# MCU.net
KiCad netlist of a schematic drawn in Altium Designer
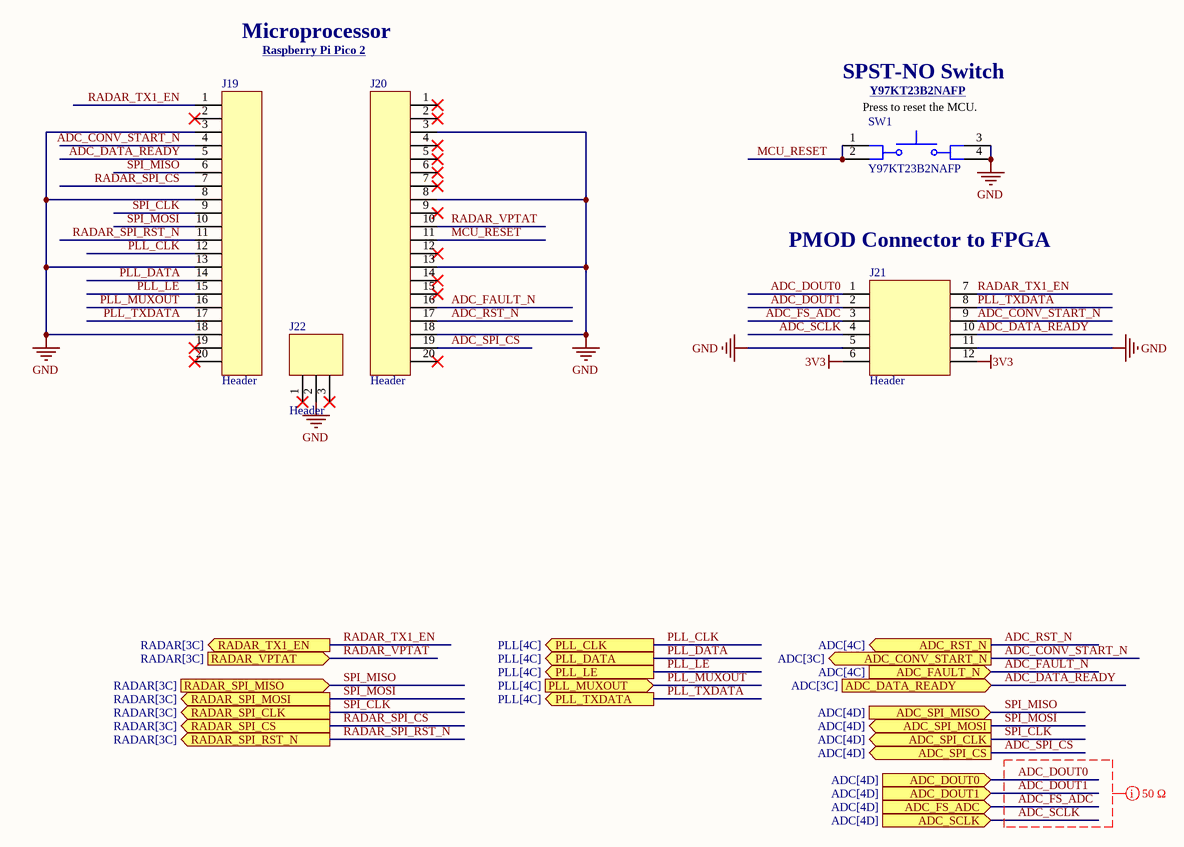
[diagram p0: MCU.SchDoc]

(export (version "E")
  (design (tool "Eeschema 10.0.6"))
  (components
    (comp (ref "J19")
      (value "Header")
      (footprint "CONN_1x20_2.54mm_PinSocket_Vertical")
      (description "WR-PHD 2.54 mm Socket Header; 20 pins")
      (fields
        (field (name "MANUFACTURER") "Wurth Elektronik")
        (field (name "MANUFACTURER PART NUMBER") "61302011821")
      )
      (libsource (lib "Titan") (part "CONN_1x20_2.54mm_PinSocket_Vertical"))
    )
    (comp (ref "J20")
      (value "Header")
      (footprint "CONN_1x20_2.54mm_PinSocket_Vertical")
      (description "WR-PHD 2.54 mm Socket Header; 20 pins")
      (fields
        (field (name "MANUFACTURER") "Wurth Elektronik")
        (field (name "MANUFACTURER PART NUMBER") "61302011821")
      )
      (libsource (lib "") (part "CONN_1x20_2.54mm_PinSocket_Vertical_1"))
    )
    (comp (ref "J21")
      (value "Header")
      (footprint "CONN_2x6_2.54mm_PinHeader_Horizontal")
      (description "Conn Unshrouded Header HDR 12 POS 2.54mm Solder RA Top Entry Thru-Hole Bag")
      (fields
        (field (name "MANUFACTURER") "Adam Tech")
        (field (name "MANUFACTURER PART NUMBER") "PH2RA-12-UA")
      )
      (libsource (lib "Titan") (part "CONN_2x6_2.54mm_PinHeader_Horizontal"))
    )
    (comp (ref "J22")
      (value "Header")
      (footprint "CONN_1x3_2.54mm_PinSocket_Vertical")
      (description "Btb Conn, Rcpt, 3Pos, 1Row, 2.54Mm Rohs Compliant: Yes ¦Wurth Elektronik 61300311821")
      (fields
        (field (name "MANUFACTURER") "Wurth Elektronik")
        (field (name "MANUFACTURER PART NUMBER") "61300311821")
      )
      (libsource (lib "Titan") (part "CONN_1x3_2.54mm_PinSocket_Vertical"))
    )
    (comp (ref "SW1")
      (value "Y97KT23B2NAFP")
      (footprint "PTS647")
      (description "Switch Tactile OFF Mom SPST Round Button Gull Wing 50mA 12VDC 100000Cycles 1.77N Surface Mount T/R")
      (fields (field (name "MANUFACTURER") "C&K"))
      (libsource (lib "Titan") (part "Y97KT23B2NAFP"))
    )
  )
  (nets
    (net (code "1") (name "/ADC_CONV_START_N") (class "Default")
      (node (ref "J19") (pin "4") (pintype "passive"))
      (node (ref "J21") (pin "9") (pintype "passive"))
    )
    (net (code "2") (name "/ADC_DATA_READY") (class "Default")
      (node (ref "J19") (pin "5") (pintype "passive"))
      (node (ref "J21") (pin "10") (pintype "passive"))
    )
    (net (code "3") (name "/ADC_DOUT0") (class "Default") (node (ref "J21") (pin "1") (pintype "passive")))
    (net (code "4") (name "/ADC_DOUT1") (class "Default") (node (ref "J21") (pin "2") (pintype "passive")))
    (net (code "5") (name "/ADC_FAULT_N") (class "Default") (node (ref "J20") (pin "16") (pintype "passive")))
    (net (code "6") (name "/ADC_FS_ADC") (class "Default") (node (ref "J21") (pin "3") (pintype "passive")))
    (net (code "7") (name "/ADC_RST_N") (class "Default") (node (ref "J20") (pin "17") (pintype "passive")))
    (net (code "8") (name "/ADC_SCLK") (class "Default") (node (ref "J21") (pin "4") (pintype "passive")))
    (net (code "9") (name "/ADC_SPI_CS") (class "Default") (node (ref "J20") (pin "19") (pintype "passive")))
    (net (code "10") (name "/MCU_RESET") (class "Default")
      (node (ref "J20") (pin "11") (pintype "passive"))
      (node (ref "SW1") (pin "1") (pintype "passive"))
      (node (ref "SW1") (pin "2") (pintype "passive"))
    )
    (net (code "11") (name "/PLL_CLK") (class "Default") (node (ref "J19") (pin "12") (pintype "passive")))
    (net (code "12") (name "/PLL_DATA") (class "Default") (node (ref "J19") (pin "14") (pintype "passive")))
    (net (code "13") (name "/PLL_LE") (class "Default") (node (ref "J19") (pin "15") (pintype "passive")))
    (net (code "14") (name "/PLL_MUXOUT") (class "Default") (node (ref "J19") (pin "16") (pintype "passive")))
    (net (code "15") (name "/PLL_TXDATA") (class "Default")
      (node (ref "J19") (pin "17") (pintype "passive"))
      (node (ref "J21") (pin "8") (pintype "passive"))
    )
    (net (code "16") (name "/RADAR_SPI_CS") (class "Default")
      (node (ref "J19") (pin "7") (pintype "passive"))
    )
    (net (code "17") (name "/RADAR_SPI_RST_N") (class "Default")
      (node (ref "J19") (pin "11") (pintype "passive"))
    )
    (net (code "18") (name "/RADAR_TX1_EN") (class "Default")
      (node (ref "J19") (pin "1") (pintype "passive"))
      (node (ref "J21") (pin "7") (pintype "passive"))
    )
    (net (code "19") (name "/RADAR_VPTAT") (class "Default")
      (node (ref "J20") (pin "10") (pintype "passive"))
    )
    (net (code "20") (name "/SPI_CLK") (class "Default") (node (ref "J19") (pin "9") (pintype "passive")))
    (net (code "21") (name "/SPI_MISO") (class "Default") (node (ref "J19") (pin "6") (pintype "passive")))
    (net (code "22") (name "/SPI_MOSI") (class "Default") (node (ref "J19") (pin "10") (pintype "passive")))
    (net (code "23") (name "3V3") (class "Default")
      (node (ref "J21") (pin "12") (pintype "passive"))
      (node (ref "J21") (pin "6") (pintype "passive"))
    )
    (net (code "24") (name "GND") (class "Default")
      (node (ref "J19") (pin "13") (pintype "passive"))
      (node (ref "J19") (pin "18") (pintype "passive"))
      (node (ref "J19") (pin "3") (pintype "passive"))
      (node (ref "J19") (pin "8") (pintype "passive"))
      (node (ref "J20") (pin "13") (pintype "passive"))
      (node (ref "J20") (pin "18") (pintype "passive"))
      (node (ref "J20") (pin "3") (pintype "passive"))
      (node (ref "J20") (pin "8") (pintype "passive"))
      (node (ref "J21") (pin "11") (pintype "passive"))
      (node (ref "J21") (pin "5") (pintype "passive"))
      (node (ref "J22") (pin "2") (pintype "passive"))
      (node (ref "SW1") (pin "3") (pintype "passive"))
      (node (ref "SW1") (pin "4") (pintype "passive"))
    )
    (net (code "25") (name "unconnected-(J19-Pad2)") (class "Default")
      (node (ref "J19") (pin "2") (pintype "passive+no_connect"))
    )
    (net (code "26") (name "unconnected-(J19-Pad19)") (class "Default")
      (node (ref "J19") (pin "19") (pintype "passive+no_connect"))
    )
    (net (code "27") (name "unconnected-(J19-Pad20)") (class "Default")
      (node (ref "J19") (pin "20") (pintype "passive+no_connect"))
    )
    (net (code "28") (name "unconnected-(J20-Pad1)") (class "Default")
      (node (ref "J20") (pin "1") (pintype "passive+no_connect"))
    )
    (net (code "29") (name "unconnected-(J20-Pad2)") (class "Default")
      (node (ref "J20") (pin "2") (pintype "passive+no_connect"))
    )
    (net (code "30") (name "unconnected-(J20-Pad4)") (class "Default")
      (node (ref "J20") (pin "4") (pintype "passive+no_connect"))
    )
    (net (code "31") (name "unconnected-(J20-Pad5)") (class "Default")
      (node (ref "J20") (pin "5") (pintype "passive+no_connect"))
    )
    (net (code "32") (name "unconnected-(J20-Pad6)") (class "Default")
      (node (ref "J20") (pin "6") (pintype "passive+no_connect"))
    )
    (net (code "33") (name "unconnected-(J20-Pad7)") (class "Default")
      (node (ref "J20") (pin "7") (pintype "passive+no_connect"))
    )
    (net (code "34") (name "unconnected-(J20-Pad9)") (class "Default")
      (node (ref "J20") (pin "9") (pintype "passive+no_connect"))
    )
    (net (code "35") (name "unconnected-(J20-Pad12)") (class "Default")
      (node (ref "J20") (pin "12") (pintype "passive+no_connect"))
    )
    (net (code "36") (name "unconnected-(J20-Pad14)") (class "Default")
      (node (ref "J20") (pin "14") (pintype "passive+no_connect"))
    )
    (net (code "37") (name "unconnected-(J20-Pad15)") (class "Default")
      (node (ref "J20") (pin "15") (pintype "passive+no_connect"))
    )
    (net (code "38") (name "unconnected-(J20-Pad20)") (class "Default")
      (node (ref "J20") (pin "20") (pintype "passive+no_connect"))
    )
    (net (code "39") (name "unconnected-(J22-Pad1)") (class "Default")
      (node (ref "J22") (pin "1") (pintype "passive+no_connect"))
    )
    (net (code "40") (name "unconnected-(J22-Pad3)") (class "Default")
      (node (ref "J22") (pin "3") (pintype "passive+no_connect"))
    )
  )
)
